# PIC32_Subsystem.net
KiCad netlist of a schematic drawn in Altium Designer
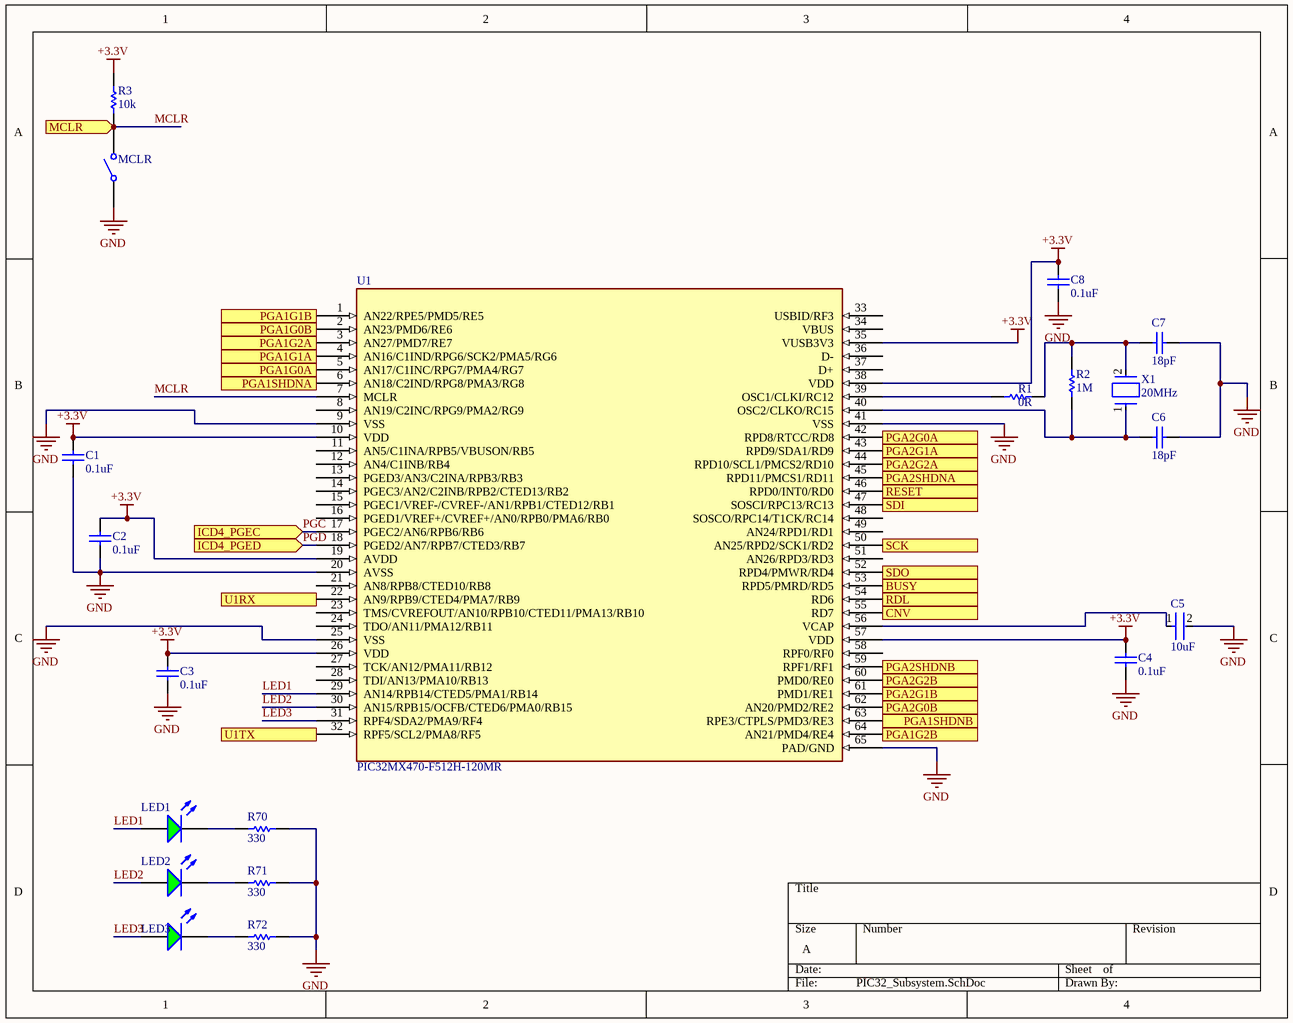
[diagram p0: PIC32_Subsystem.SchDoc]

(export (version "E")
  (design (tool "Eeschema 10.0.6"))
  (components
    (comp (ref "C1")
      (value "0.1uF")
      (footprint "CAPC1050X55X23ML05T13")
      (fields (field (name "MANUFACTURER") "Samsung Electro-Mechanics"))
      (libsource (lib "Altium Content Vault") (part "CAP-NP-2"))
    )
    (comp (ref "C2")
      (value "0.1uF")
      (footprint "CAPC1050X55X23ML05T13")
      (fields (field (name "MANUFACTURER") "Samsung Electro-Mechanics"))
      (libsource (lib "Altium Content Vault") (part "CAP-NP-2"))
    )
    (comp (ref "C3")
      (value "0.1uF")
      (footprint "CAPC1050X55X23ML05T13")
      (fields (field (name "MANUFACTURER") "Samsung Electro-Mechanics"))
      (libsource (lib "Altium Content Vault") (part "CAP-NP-2"))
    )
    (comp (ref "C4")
      (value "0.1uF")
      (footprint "CAPC1050X55X23ML05T13")
      (fields (field (name "MANUFACTURER") "Samsung Electro-Mechanics"))
      (libsource (lib "Altium Content Vault") (part "CAP-NP-2"))
    )
    (comp (ref "C5")
      (value "10uF")
      (footprint "FP-GRM188-0_1-e0_2_0_55-IPC_A")
      (fields (field (name "VOLTAGE") "6.3V") (field (name "TOLERANCE") "20%"))
      (libsource (lib "Altium Content Vault") (part "02cd4be3c70576c341d710602a673aa"))
    )
    (comp (ref "C6")
      (value "18pF")
      (footprint "CAPC1005X55X25LL05T10")
      (description "GRM1555C1H180GA01D")
      (fields (field (name "MANUFACTURER") "Murata"))
      (libsource (lib "Altium Content Vault") (part "CAP"))
    )
    (comp (ref "C7")
      (value "18pF")
      (footprint "CAPC1005X55X25LL05T10")
      (description "GRM1555C1H180GA01D")
      (fields (field (name "MANUFACTURER") "Murata"))
      (libsource (lib "Altium Content Vault") (part "CAP"))
    )
    (comp (ref "C8")
      (value "0.1uF")
      (footprint "CAPC1050X55X23ML05T13")
      (fields (field (name "MANUFACTURER") "Samsung Electro-Mechanics"))
      (libsource (lib "Altium Content Vault") (part "CAP-NP-2"))
    )
    (comp (ref "LED1")
      (value "~")
      (footprint "KING-APT1608SGC_V")
      (description "Super Bright Green LED, 62.5 mW, 25 mA, -40 to 85 degC, 2-Pin SMD, RoHS, Tape and Reel, APT1608SGC")
      (fields (field (name "MANUFACTURER") "Kingbright"))
      (libsource (lib "Altium Content Vault") (part "LED-GREEN-AK-2"))
    )
    (comp (ref "LED2")
      (value "~")
      (footprint "KING-APT1608SGC_V")
      (description "Super Bright Green LED, 62.5 mW, 25 mA, -40 to 85 degC, 2-Pin SMD, RoHS, Tape and Reel, APT1608SGC")
      (fields (field (name "MANUFACTURER") "Kingbright"))
      (libsource (lib "Altium Content Vault") (part "LED-GREEN-AK-2"))
    )
    (comp (ref "LED3")
      (value "~")
      (footprint "KING-APT1608SGC_V")
      (description "Super Bright Green LED, 62.5 mW, 25 mA, -40 to 85 degC, 2-Pin SMD, RoHS, Tape and Reel, APT1608SGC")
      (fields (field (name "MANUFACTURER") "Kingbright"))
      (libsource (lib "Altium Content Vault") (part "LED-GREEN-AK-2"))
    )
    (comp (ref "MCLR")
      (value "434121043816")
      (footprint "434121043816")
      (description "WS-TASV SMD Tact Switch 6.0X3.5 mm")
      (fields (field (name "MANUFACTURER") "Wuerth Elektronik"))
      (libsource (lib "Altium Content Vault") (part "WE-TACT-SW-2"))
    )
    (comp (ref "R1")
      (value "0R")
      (footprint "RESC1005X40X25NL05T10")
      (description "RC0402JR-070RL")
      (fields (field (name "MANUFACTURER") "Yageo / Phycomp"))
      (libsource (lib "Altium Content Vault") (part "RES"))
    )
    (comp (ref "R2")
      (value "1M")
      (footprint "RESC1005X40X25LL05T05")
      (fields
        (field (name "PARTNUMBER") "ERJ-2RKF1004X")
        (field (name "TOLERANCE") "1%")
        (field (name "MANUFACTURER") "Basic Passives")
      )
      (libsource (lib "Altium Content Vault") (part "RES-2"))
    )
    (comp (ref "R3")
      (value "10k")
      (footprint "RESC1005X40X25LL05T05")
      (fields (field (name "TOLERANCE") "1%") (field (name "MANUFACTURER") "Panasonic"))
      (libsource (lib "Altium Content Vault") (part "RES-2"))
    )
    (comp (ref "R70")
      (value "330")
      (footprint "RESC1609X50X30LL10T20")
      (description "CRCW0603330RJNEA")
      (fields (field (name "MANUFACTURER") "Vishay Dale"))
      (libsource (lib "Altium Content Vault") (part "RES"))
    )
    (comp (ref "R71")
      (value "330")
      (footprint "RESC1609X50X30LL10T20")
      (description "CRCW0603330RJNEA")
      (fields (field (name "MANUFACTURER") "Vishay Dale"))
      (libsource (lib "Altium Content Vault") (part "RES"))
    )
    (comp (ref "R72")
      (value "330")
      (footprint "RESC1609X50X30LL10T20")
      (description "CRCW0603330RJNEA")
      (fields (field (name "MANUFACTURER") "Vishay Dale"))
      (libsource (lib "Altium Content Vault") (part "RES"))
    )
    (comp (ref "U1")
      (value "PIC32MX470-F512H-120MR")
      (footprint "TQFP")
      (libsource (lib "PIC32MX470-F512H-120MR") (part "PIC32MX470-F512H-120MR"))
    )
    (comp (ref "X1")
      (value "20MHz")
      (footprint "FP-ABM7-MFG")
      (description "Crystal 20MHz ±20ppm 18pF SMD-2 6mm x 3.5mm\r\nABM7-20.000MHZ-D2Y-T")
      (fields (field (name "TOLERANCE") "20ppm"))
      (libsource (lib "Altium Content Vault") (part "c23a69dc6c9e2f18f2079038eb95dd1"))
    )
  )
  (nets
    (net (code "1") (name "+3.3V") (class "Default")
      (node (ref "C1") (pin "2") (pinfunction "2_2") (pintype "passive"))
      (node (ref "C2") (pin "2") (pinfunction "2_2") (pintype "passive"))
      (node (ref "C3") (pin "2") (pinfunction "2_2") (pintype "passive"))
      (node (ref "C4") (pin "2") (pinfunction "2_2") (pintype "passive"))
      (node (ref "C8") (pin "2") (pinfunction "2_2") (pintype "passive"))
      (node (ref "R3") (pin "2") (pinfunction "2_2") (pintype "passive"))
      (node (ref "U1") (pin "10") (pinfunction "VDD_10") (pintype "input"))
      (node (ref "U1") (pin "19") (pinfunction "AVDD_19") (pintype "input"))
      (node (ref "U1") (pin "26") (pinfunction "VDD_26") (pintype "input"))
      (node (ref "U1") (pin "35") (pinfunction "VUSB3V3_35") (pintype "input"))
      (node (ref "U1") (pin "38") (pinfunction "VDD_38") (pintype "input"))
      (node (ref "U1") (pin "57") (pinfunction "VDD_57") (pintype "input"))
    )
    (net (code "2") (name "/BUSY") (class "Default")
      (node (ref "U1") (pin "53") (pinfunction "RPD5/PMRD/RD5_53") (pintype "input"))
    )
    (net (code "3") (name "/CNV") (class "Default")
      (node (ref "U1") (pin "55") (pinfunction "RD7_55") (pintype "input"))
    )
    (net (code "4") (name "/LED1") (class "Default")
      (node (ref "LED1") (pin "1") (pinfunction "A_1") (pintype "passive"))
      (node (ref "U1") (pin "29") (pinfunction "AN14/RPB14/CTED5/PMA1/RB14_29") (pintype "input"))
    )
    (net (code "5") (name "/LED2") (class "Default")
      (node (ref "LED2") (pin "1") (pinfunction "A_1") (pintype "passive"))
      (node (ref "U1") (pin "30") (pinfunction "AN15/RPB15/OCFB/CTED6/PMA0/RB15_30") (pintype "input"))
    )
    (net (code "6") (name "/LED3") (class "Default")
      (node (ref "LED3") (pin "1") (pinfunction "A_1") (pintype "passive"))
      (node (ref "U1") (pin "31") (pinfunction "RPF4/SDA2/PMA9/RF4_31") (pintype "input"))
    )
    (net (code "7") (name "/MCLR") (class "Default")
      (node (ref "MCLR") (pin "2") (pinfunction "2_2") (pintype "passive"))
      (node (ref "R3") (pin "1") (pinfunction "1_1") (pintype "passive"))
      (node (ref "U1") (pin "7") (pinfunction "MCLR_7") (pintype "input"))
    )
    (net (code "8") (name "/PGA1G0A") (class "Default")
      (node (ref "U1") (pin "5") (pinfunction "AN17/C1INC/RPG7/PMA4/RG7_5") (pintype "input"))
    )
    (net (code "9") (name "/PGA1G0B") (class "Default")
      (node (ref "U1") (pin "2") (pinfunction "AN23/PMD6/RE6_2") (pintype "input"))
    )
    (net (code "10") (name "/PGA1G1A") (class "Default")
      (node (ref "U1") (pin "4") (pinfunction "AN16/C1IND/RPG6/SCK2/PMA5/RG6_4") (pintype "input"))
    )
    (net (code "11") (name "/PGA1G1B") (class "Default")
      (node (ref "U1") (pin "1") (pinfunction "AN22/RPE5/PMD5/RE5_1") (pintype "input"))
    )
    (net (code "12") (name "/PGA1G2A") (class "Default")
      (node (ref "U1") (pin "3") (pinfunction "AN27/PMD7/RE7_3") (pintype "input"))
    )
    (net (code "13") (name "/PGA1G2B") (class "Default")
      (node (ref "U1") (pin "64") (pinfunction "AN21/PMD4/RE4_64") (pintype "input"))
    )
    (net (code "14") (name "/PGA1SHDNA") (class "Default")
      (node (ref "U1") (pin "6") (pinfunction "AN18/C2IND/RPG8/PMA3/RG8_6") (pintype "input"))
    )
    (net (code "15") (name "/PGA1SHDNB") (class "Default")
      (node (ref "U1") (pin "63") (pinfunction "RPE3/CTPLS/PMD3/RE3_63") (pintype "input"))
    )
    (net (code "16") (name "/PGA2G0A") (class "Default")
      (node (ref "U1") (pin "42") (pinfunction "RPD8/RTCC/RD8_42") (pintype "input"))
    )
    (net (code "17") (name "/PGA2G0B") (class "Default")
      (node (ref "U1") (pin "62") (pinfunction "AN20/PMD2/RE2_62") (pintype "input"))
    )
    (net (code "18") (name "/PGA2G1A") (class "Default")
      (node (ref "U1") (pin "43") (pinfunction "RPD9/SDA1/RD9_43") (pintype "input"))
    )
    (net (code "19") (name "/PGA2G1B") (class "Default")
      (node (ref "U1") (pin "61") (pinfunction "PMD1/RE1_61") (pintype "input"))
    )
    (net (code "20") (name "/PGA2G2A") (class "Default")
      (node (ref "U1") (pin "44") (pinfunction "RPD10/SCL1/PMCS2/RD10_44") (pintype "input"))
    )
    (net (code "21") (name "/PGA2G2B") (class "Default")
      (node (ref "U1") (pin "60") (pinfunction "PMD0/RE0_60") (pintype "input"))
    )
    (net (code "22") (name "/PGA2SHDNA") (class "Default")
      (node (ref "U1") (pin "45") (pinfunction "RPD11/PMCS1/RD11_45") (pintype "input"))
    )
    (net (code "23") (name "/PGA2SHDNB") (class "Default")
      (node (ref "U1") (pin "59") (pinfunction "RPF1/RF1_59") (pintype "input"))
    )
    (net (code "24") (name "/PGC") (class "Default")
      (node (ref "U1") (pin "17") (pinfunction "PGEC2/AN6/RPB6/RB6_17") (pintype "input"))
    )
    (net (code "25") (name "/PGD") (class "Default")
      (node (ref "U1") (pin "18") (pinfunction "PGED2/AN7/RPB7/CTED3/RB7_18") (pintype "input"))
    )
    (net (code "26") (name "/RDL") (class "Default")
      (node (ref "U1") (pin "54") (pinfunction "RD6_54") (pintype "input"))
    )
    (net (code "27") (name "/RESET") (class "Default")
      (node (ref "U1") (pin "46") (pinfunction "RPD0/INT0/RD0_46") (pintype "input"))
    )
    (net (code "28") (name "/SCK") (class "Default")
      (node (ref "U1") (pin "50") (pinfunction "AN25/RPD2/SCK1/RD2_50") (pintype "input"))
    )
    (net (code "29") (name "/SDI") (class "Default")
      (node (ref "U1") (pin "47") (pinfunction "SOSCI/RPC13/RC13_47") (pintype "input"))
    )
    (net (code "30") (name "/SDO") (class "Default")
      (node (ref "U1") (pin "52") (pinfunction "RPD4/PMWR/RD4_52") (pintype "input"))
    )
    (net (code "31") (name "/U1RX") (class "Default")
      (node (ref "U1") (pin "22") (pinfunction "AN9/RPB9/CTED4/PMA7/RB9_22") (pintype "input"))
    )
    (net (code "32") (name "/U1TX") (class "Default")
      (node (ref "U1") (pin "32") (pinfunction "RPF5/SCL2/PMA8/RF5_32") (pintype "input"))
    )
    (net (code "33") (name "GND") (class "Default")
      (node (ref "C1") (pin "1") (pinfunction "1_1") (pintype "passive"))
      (node (ref "C2") (pin "1") (pinfunction "1_1") (pintype "passive"))
      (node (ref "C3") (pin "1") (pinfunction "1_1") (pintype "passive"))
      (node (ref "C4") (pin "1") (pinfunction "1_1") (pintype "passive"))
      (node (ref "C5") (pin "2") (pinfunction "2_2") (pintype "passive"))
      (node (ref "C6") (pin "2") (pinfunction "2_2") (pintype "passive"))
      (node (ref "C7") (pin "2") (pinfunction "2_2") (pintype "passive"))
      (node (ref "C8") (pin "1") (pinfunction "1_1") (pintype "passive"))
      (node (ref "MCLR") (pin "1") (pinfunction "1_1") (pintype "passive"))
      (node (ref "R70") (pin "2") (pinfunction "2_2") (pintype "passive"))
      (node (ref "R71") (pin "2") (pinfunction "2_2") (pintype "passive"))
      (node (ref "R72") (pin "2") (pinfunction "2_2") (pintype "passive"))
      (node (ref "U1") (pin "20") (pinfunction "AVSS_20") (pintype "input"))
      (node (ref "U1") (pin "25") (pinfunction "VSS_25") (pintype "input"))
      (node (ref "U1") (pin "41") (pinfunction "VSS_41") (pintype "input"))
      (node (ref "U1") (pin "65") (pinfunction "PAD/GND_65") (pintype "input"))
      (node (ref "U1") (pin "9") (pinfunction "VSS_9") (pintype "input"))
    )
    (net (code "34") (name "Net-(C7-Pad1)") (class "Default")
      (node (ref "C7") (pin "1") (pinfunction "1_1") (pintype "passive"))
      (node (ref "R1") (pin "2") (pinfunction "2_2") (pintype "passive"))
      (node (ref "R2") (pin "2") (pinfunction "2_2") (pintype "passive"))
      (node (ref "X1") (pin "2") (pinfunction "2_2") (pintype "passive"))
    )
    (net (code "35") (name "Net-(LED1-K)") (class "Default")
      (node (ref "LED1") (pin "2") (pinfunction "K_2") (pintype "passive"))
      (node (ref "R70") (pin "1") (pinfunction "1_1") (pintype "passive"))
    )
    (net (code "36") (name "Net-(LED2-K)") (class "Default")
      (node (ref "LED2") (pin "2") (pinfunction "K_2") (pintype "passive"))
      (node (ref "R71") (pin "1") (pinfunction "1_1") (pintype "passive"))
    )
    (net (code "37") (name "Net-(LED3-K)") (class "Default")
      (node (ref "LED3") (pin "2") (pinfunction "K_2") (pintype "passive"))
      (node (ref "R72") (pin "1") (pinfunction "1_1") (pintype "passive"))
    )
    (net (code "38") (name "Net-(U1-OSC1{slash}CLKI{slash}RC12)") (class "Default")
      (node (ref "R1") (pin "1") (pinfunction "1_1") (pintype "passive"))
      (node (ref "U1") (pin "39") (pinfunction "OSC1/CLKI/RC12_39") (pintype "input"))
    )
    (net (code "39") (name "Net-(U1-OSC2{slash}CLKO{slash}RC15)") (class "Default")
      (node (ref "C6") (pin "1") (pinfunction "1_1") (pintype "passive"))
      (node (ref "R2") (pin "1") (pinfunction "1_1") (pintype "passive"))
      (node (ref "U1") (pin "40") (pinfunction "OSC2/CLKO/RC15_40") (pintype "input"))
      (node (ref "X1") (pin "1") (pinfunction "1_1") (pintype "passive"))
    )
    (net (code "40") (name "Net-(U1-VCAP)") (class "Default")
      (node (ref "C5") (pin "1") (pinfunction "1_1") (pintype "passive"))
      (node (ref "U1") (pin "56") (pinfunction "VCAP_56") (pintype "input"))
    )
    (net (code "41") (name "unconnected-(U1-AN4{slash}C1INB{slash}RB4-Pad12)") (class "Default")
      (node (ref "U1") (pin "12") (pinfunction "AN4/C1INB/RB4_12") (pintype "input"))
    )
    (net (code "42") (name "unconnected-(U1-AN5{slash}C1INA{slash}RPB5{slash}VBUSON{slash}RB5-Pad11)") (class "Default")
      (node (ref "U1") (pin "11") (pinfunction "AN5/C1INA/RPB5/VBUSON/RB5_11") (pintype "input"))
    )
    (net (code "43") (name "unconnected-(U1-AN8{slash}RPB8{slash}CTED10{slash}RB8-Pad21)") (class "Default")
      (node (ref "U1") (pin "21") (pinfunction "AN8/RPB8/CTED10/RB8_21") (pintype "input"))
    )
    (net (code "44") (name "unconnected-(U1-AN19{slash}C2INC{slash}RPG9{slash}PMA2{slash}RG9-Pad8)") (class "Default")
      (node (ref "U1") (pin "8") (pinfunction "AN19/C2INC/RPG9/PMA2/RG9_8") (pintype "input"))
    )
    (net (code "45") (name "unconnected-(U1-AN24{slash}RPD1{slash}RD1-Pad49)") (class "Default")
      (node (ref "U1") (pin "49") (pinfunction "AN24/RPD1/RD1_49") (pintype "input"))
    )
    (net (code "46") (name "unconnected-(U1-AN26{slash}RPD3{slash}RD3-Pad51)") (class "Default")
      (node (ref "U1") (pin "51") (pinfunction "AN26/RPD3/RD3_51") (pintype "input"))
    )
    (net (code "47") (name "unconnected-(U1-D+-Pad37)") (class "Default")
      (node (ref "U1") (pin "37") (pinfunction "D+_37") (pintype "input"))
    )
    (net (code "48") (name "unconnected-(U1-D--Pad36)") (class "Default")
      (node (ref "U1") (pin "36") (pinfunction "D-_36") (pintype "input"))
    )
    (net (code "49") (name "unconnected-(U1-PGEC1{slash}VREF-{slash}CVREF-{slash}AN1{slash}RPB1{slash}CTED12{slash}RB1-Pad15)") (class "Default")
      (node (ref "U1") (pin "15") (pinfunction "PGEC1/VREF-/CVREF-/AN1/RPB1/CTED12/RB1_15") (pintype "input"))
    )
    (net (code "50") (name "unconnected-(U1-PGEC3{slash}AN2{slash}C2INB{slash}RPB2{slash}CTED13{slash}RB2-Pad14)") (class "Default")
      (node (ref "U1") (pin "14") (pinfunction "PGEC3/AN2/C2INB/RPB2/CTED13/RB2_14") (pintype "input"))
    )
    (net (code "51") (name "unconnected-(U1-PGED1{slash}VREF+{slash}CVREF+{slash}AN0{slash}RPB0{slash}PMA6{slash}RB0-Pad16)") (class "Default")
      (node (ref "U1") (pin "16") (pinfunction "PGED1/VREF+/CVREF+/AN0/RPB0/PMA6/RB0_16") (pintype "input"))
    )
    (net (code "52") (name "unconnected-(U1-PGED3{slash}AN3{slash}C2INA{slash}RPB3{slash}RB3-Pad13)") (class "Default")
      (node (ref "U1") (pin "13") (pinfunction "PGED3/AN3/C2INA/RPB3/RB3_13") (pintype "input"))
    )
    (net (code "53") (name "unconnected-(U1-RPF0{slash}RF0-Pad58)") (class "Default")
      (node (ref "U1") (pin "58") (pinfunction "RPF0/RF0_58") (pintype "input"))
    )
    (net (code "54") (name "unconnected-(U1-SOSCO{slash}RPC14{slash}T1CK{slash}RC14-Pad48)") (class "Default")
      (node (ref "U1") (pin "48") (pinfunction "SOSCO/RPC14/T1CK/RC14_48") (pintype "input"))
    )
    (net (code "55") (name "unconnected-(U1-TCK{slash}AN12{slash}PMA11{slash}RB12-Pad27)") (class "Default")
      (node (ref "U1") (pin "27") (pinfunction "TCK/AN12/PMA11/RB12_27") (pintype "input"))
    )
    (net (code "56") (name "unconnected-(U1-TDI{slash}AN13{slash}PMA10{slash}RB13-Pad28)") (class "Default")
      (node (ref "U1") (pin "28") (pinfunction "TDI/AN13/PMA10/RB13_28") (pintype "input"))
    )
    (net (code "57") (name "unconnected-(U1-TDO{slash}AN11{slash}PMA12{slash}RB11-Pad24)") (class "Default")
      (node (ref "U1") (pin "24") (pinfunction "TDO/AN11/PMA12/RB11_24") (pintype "input"))
    )
    (net (code "58") (name "unconnected-(U1-TMS{slash}CVREFOUT{slash}AN10{slash}RPB10{slash}CTED11{slash}PMA13{slash}RB10-Pad23)") (class "Default")
      (node (ref "U1") (pin "23") (pinfunction "TMS/CVREFOUT/AN10/RPB10/CTED11/PMA13/RB10_23") (pintype "input"))
    )
    (net (code "59") (name "unconnected-(U1-USBID{slash}RF3-Pad33)") (class "Default")
      (node (ref "U1") (pin "33") (pinfunction "USBID/RF3_33") (pintype "input"))
    )
    (net (code "60") (name "unconnected-(U1-VBUS-Pad34)") (class "Default")
      (node (ref "U1") (pin "34") (pinfunction "VBUS_34") (pintype "input"))
    )
  )
)
